# board-led.net
KiCad netlist of a schematic drawn in EAGLE
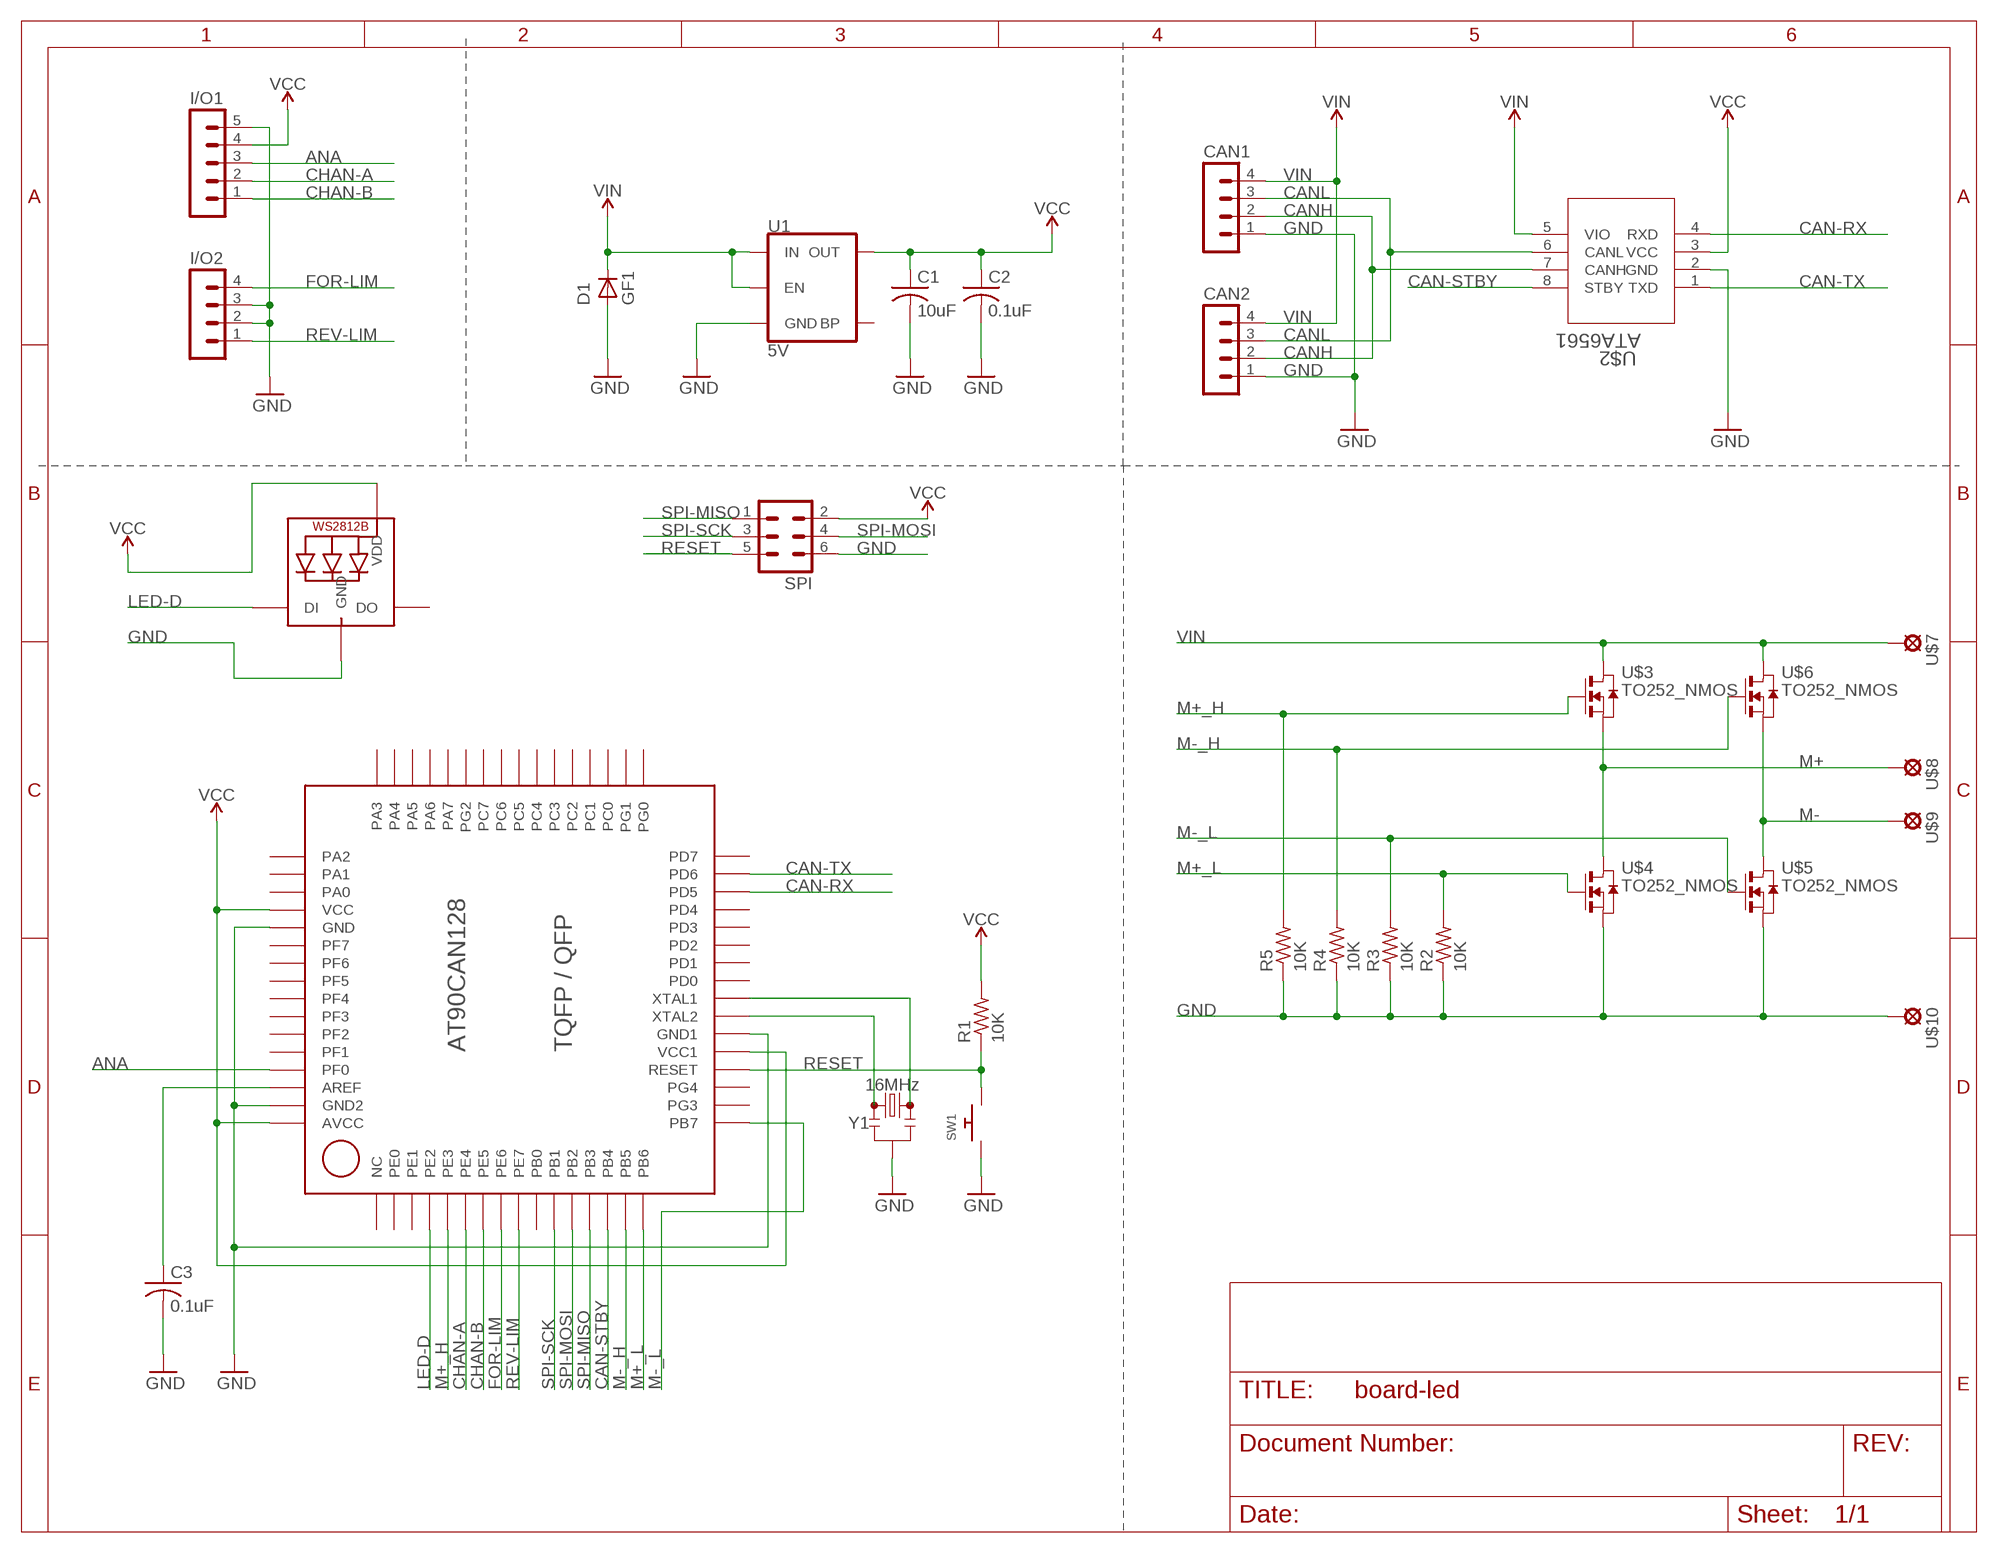
[diagram p0: schematic, sheet 1]

(export (version "E")
  (design (tool "Eeschema 10.0.6"))
  (components
    (comp (ref "C1")
      (value "10uF")
      (footprint "eagle-import:C0603")
      (libsource (lib "eagle-import") (part "C-USC0603"))
    )
    (comp (ref "C2")
      (value "0.1uF")
      (footprint "eagle-import:C0603")
      (libsource (lib "eagle-import") (part "C-USC0603"))
    )
    (comp (ref "C3")
      (value "0.1uF")
      (footprint "eagle-import:C0603")
      (libsource (lib "eagle-import") (part "C-USC0603"))
    )
    (comp (ref "CAN1")
      (value "MA04-1")
      (footprint "eagle-import:MA04-1")
      (libsource (lib "eagle-import") (part "MA04-1"))
    )
    (comp (ref "CAN2")
      (value "MA04-1")
      (footprint "eagle-import:MA04-1")
      (libsource (lib "eagle-import") (part "MA04-1"))
    )
    (comp (ref "D1")
      (value "GF1")
      (footprint "eagle-import:SMA-DO214AC")
      (libsource (lib "eagle-import") (part "GF1"))
    )
    (comp (ref "I/O1")
      (value "MA05-1")
      (footprint "eagle-import:MA05-1")
      (libsource (lib "eagle-import") (part "MA05-1"))
    )
    (comp (ref "I/O2")
      (value "MA04-1")
      (footprint "eagle-import:MA04-1")
      (libsource (lib "eagle-import") (part "MA04-1"))
    )
    (comp (ref "LED1")
      (value "WS2812B3535")
      (footprint "eagle-import:LED3535")
      (libsource (lib "eagle-import") (part "WS2812B3535"))
    )
    (comp (ref "R1")
      (value "10K")
      (footprint "eagle-import:R0603")
      (libsource (lib "eagle-import") (part "R-US_R0603"))
    )
    (comp (ref "R2")
      (value "10K")
      (footprint "eagle-import:R0603")
      (libsource (lib "eagle-import") (part "R-US_R0603"))
    )
    (comp (ref "R3")
      (value "10K")
      (footprint "eagle-import:R0603")
      (libsource (lib "eagle-import") (part "R-US_R0603"))
    )
    (comp (ref "R4")
      (value "10K")
      (footprint "eagle-import:R0603")
      (libsource (lib "eagle-import") (part "R-US_R0603"))
    )
    (comp (ref "R5")
      (value "10K")
      (footprint "eagle-import:R0603")
      (libsource (lib "eagle-import") (part "R-US_R0603"))
    )
    (comp (ref "SPI")
      (value "MA03-2")
      (footprint "eagle-import:MA03-2")
      (libsource (lib "eagle-import") (part "MA03-2"))
    )
    (comp (ref "SW1")
      (value "SWITCH_PUSHBUTTONEVQ-PE")
      (footprint "eagle-import:TACT_PANA-EVQ")
      (libsource (lib "eagle-import") (part "SWITCH_PUSHBUTTONEVQ-PE"))
    )
    (comp (ref "U$1")
      (value "AT90CAN128")
      (footprint "eagle-import:QFP64_TQFP64")
      (libsource (lib "eagle-import") (part "AT90CAN128"))
    )
    (comp (ref "U$2")
      (value "ATA6561")
      (footprint "eagle-import:SO8")
      (libsource (lib "eagle-import") (part "ATA6561"))
    )
    (comp (ref "U$3")
      (value "TO252_NMOS")
      (footprint "eagle-import:TO252")
      (libsource (lib "eagle-import") (part "TO252_NMOS"))
    )
    (comp (ref "U$4")
      (value "TO252_NMOS")
      (footprint "eagle-import:TO252")
      (libsource (lib "eagle-import") (part "TO252_NMOS"))
    )
    (comp (ref "U$5")
      (value "TO252_NMOS")
      (footprint "eagle-import:TO252")
      (libsource (lib "eagle-import") (part "TO252_NMOS"))
    )
    (comp (ref "U$6")
      (value "TO252_NMOS")
      (footprint "eagle-import:TO252")
      (libsource (lib "eagle-import") (part "TO252_NMOS"))
    )
    (comp (ref "U$7")
      (value "SOLPAD")
      (footprint "eagle-import:SOLPAD")
      (libsource (lib "eagle-import") (part "SOLPAD"))
    )
    (comp (ref "U$8")
      (value "SOLPAD")
      (footprint "eagle-import:SOLPAD")
      (libsource (lib "eagle-import") (part "SOLPAD"))
    )
    (comp (ref "U$9")
      (value "SOLPAD")
      (footprint "eagle-import:SOLPAD")
      (libsource (lib "eagle-import") (part "SOLPAD"))
    )
    (comp (ref "U$10")
      (value "SOLPAD")
      (footprint "eagle-import:SOLPAD")
      (libsource (lib "eagle-import") (part "SOLPAD"))
    )
    (comp (ref "U1")
      (value "5V")
      (footprint "eagle-import:SOT23-5")
      (libsource (lib "eagle-import") (part "V_REG_MIC52055V"))
    )
    (comp (ref "Y1")
      (value "16MHz")
      (footprint "eagle-import:RESONATOR-SMD-3.2X1.3")
      (libsource (lib "eagle-import") (part "RESONATOR-16MHZSMD_3.2X1.3"))
    )
  )
  (nets
    (net (code "1") (name "/ANA") (class "Default")
      (node (ref "I/O1") (pin "3") (pinfunction "3_3") (pintype "passive"))
      (node (ref "U$1") (pin "61") (pinfunction "PF0_61") (pintype "bidirectional"))
    )
    (net (code "2") (name "/CAN-RX") (class "Default")
      (node (ref "U$1") (pin "30") (pinfunction "PD5_30") (pintype "bidirectional"))
      (node (ref "U$2") (pin "4") (pinfunction "RXD_4") (pintype "input"))
    )
    (net (code "3") (name "/CAN-STBY") (class "Default")
      (node (ref "U$1") (pin "14") (pinfunction "PB4_14") (pintype "bidirectional"))
      (node (ref "U$2") (pin "8") (pinfunction "STBY_8") (pintype "passive"))
    )
    (net (code "4") (name "/CAN-TX") (class "Default")
      (node (ref "U$1") (pin "31") (pinfunction "PD6_31") (pintype "bidirectional"))
      (node (ref "U$2") (pin "1") (pinfunction "TXD_1") (pintype "power_in"))
    )
    (net (code "5") (name "/CANH") (class "Default")
      (node (ref "CAN1") (pin "2") (pinfunction "2_2") (pintype "passive"))
      (node (ref "CAN2") (pin "2") (pinfunction "2_2") (pintype "passive"))
      (node (ref "U$2") (pin "7") (pinfunction "CANH_7") (pintype "output"))
    )
    (net (code "6") (name "/CANL") (class "Default")
      (node (ref "CAN1") (pin "3") (pinfunction "3_3") (pintype "passive"))
      (node (ref "CAN2") (pin "3") (pinfunction "3_3") (pintype "passive"))
      (node (ref "U$2") (pin "6") (pinfunction "CANL_6") (pintype "output"))
    )
    (net (code "7") (name "/CHAN-A") (class "Default")
      (node (ref "I/O1") (pin "2") (pinfunction "2_2") (pintype "passive"))
      (node (ref "U$1") (pin "6") (pinfunction "PE4_6") (pintype "bidirectional"))
    )
    (net (code "8") (name "/CHAN-B") (class "Default")
      (node (ref "I/O1") (pin "1") (pinfunction "1_1") (pintype "passive"))
      (node (ref "U$1") (pin "7") (pinfunction "PE5_7") (pintype "bidirectional"))
    )
    (net (code "9") (name "/FOR-LIM") (class "Default")
      (node (ref "I/O2") (pin "4") (pinfunction "4_4") (pintype "passive"))
      (node (ref "U$1") (pin "8") (pinfunction "PE6_8") (pintype "bidirectional"))
    )
    (net (code "10") (name "/LED-D") (class "Default")
      (node (ref "LED1") (pin "1") (pinfunction "DI_1") (pintype "input"))
      (node (ref "U$1") (pin "4") (pinfunction "PE2_4") (pintype "bidirectional"))
    )
    (net (code "11") (name "/M+") (class "Default")
      (node (ref "U$3") (pin "2") (pinfunction "S_2") (pintype "passive"))
      (node (ref "U$4") (pin "3") (pinfunction "D_3") (pintype "passive"))
      (node (ref "U$8") (pin "P$1") (pinfunction "MP_P$1") (pintype "passive"))
    )
    (net (code "12") (name "/M+_H") (class "Default")
      (node (ref "R5") (pin "2") (pinfunction "2_2") (pintype "passive"))
      (node (ref "U$1") (pin "5") (pinfunction "PE3_5") (pintype "bidirectional"))
      (node (ref "U$3") (pin "1") (pinfunction "G_1") (pintype "passive"))
    )
    (net (code "13") (name "/M+_L") (class "Default")
      (node (ref "R2") (pin "2") (pinfunction "2_2") (pintype "passive"))
      (node (ref "U$1") (pin "16") (pinfunction "PB6_16") (pintype "bidirectional"))
      (node (ref "U$4") (pin "1") (pinfunction "G_1") (pintype "passive"))
    )
    (net (code "14") (name "/M-") (class "Default")
      (node (ref "U$5") (pin "3") (pinfunction "D_3") (pintype "passive"))
      (node (ref "U$6") (pin "2") (pinfunction "S_2") (pintype "passive"))
      (node (ref "U$9") (pin "P$1") (pinfunction "MP_P$1") (pintype "passive"))
    )
    (net (code "15") (name "/M-_H") (class "Default")
      (node (ref "R4") (pin "2") (pinfunction "2_2") (pintype "passive"))
      (node (ref "U$1") (pin "15") (pinfunction "PB5_15") (pintype "bidirectional"))
      (node (ref "U$6") (pin "1") (pinfunction "G_1") (pintype "passive"))
    )
    (net (code "16") (name "/M-_L") (class "Default")
      (node (ref "R3") (pin "2") (pinfunction "2_2") (pintype "passive"))
      (node (ref "U$1") (pin "17") (pinfunction "PB7_17") (pintype "bidirectional"))
      (node (ref "U$5") (pin "1") (pinfunction "G_1") (pintype "passive"))
    )
    (net (code "17") (name "/RESET") (class "Default")
      (node (ref "R1") (pin "1") (pinfunction "1_1") (pintype "passive"))
      (node (ref "SPI") (pin "5") (pinfunction "5_5") (pintype "passive"))
      (node (ref "SW1") (pin "P$2") (pinfunction "P$2_P$2") (pintype "passive"))
      (node (ref "U$1") (pin "20") (pinfunction "RESET_20") (pintype "bidirectional"))
    )
    (net (code "18") (name "/REV-LIM") (class "Default")
      (node (ref "I/O2") (pin "1") (pinfunction "1_1") (pintype "passive"))
      (node (ref "U$1") (pin "9") (pinfunction "PE7_9") (pintype "bidirectional"))
    )
    (net (code "19") (name "/SPI-MISO") (class "Default")
      (node (ref "SPI") (pin "1") (pinfunction "1_1") (pintype "passive"))
      (node (ref "U$1") (pin "13") (pinfunction "PB3_13") (pintype "bidirectional"))
    )
    (net (code "20") (name "/SPI-MOSI") (class "Default")
      (node (ref "SPI") (pin "4") (pinfunction "4_4") (pintype "passive"))
      (node (ref "U$1") (pin "12") (pinfunction "PB2_12") (pintype "bidirectional"))
    )
    (net (code "21") (name "/SPI-SCK") (class "Default")
      (node (ref "SPI") (pin "3") (pinfunction "3_3") (pintype "passive"))
      (node (ref "U$1") (pin "11") (pinfunction "PB1_11") (pintype "bidirectional"))
    )
    (net (code "22") (name "GND") (class "Default")
      (node (ref "C1") (pin "2") (pinfunction "2_2") (pintype "passive"))
      (node (ref "C2") (pin "2") (pinfunction "2_2") (pintype "passive"))
      (node (ref "C3") (pin "2") (pinfunction "2_2") (pintype "passive"))
      (node (ref "CAN1") (pin "1") (pinfunction "1_1") (pintype "passive"))
      (node (ref "CAN2") (pin "1") (pinfunction "1_1") (pintype "passive"))
      (node (ref "D1") (pin "A") (pinfunction "A_A") (pintype "passive"))
      (node (ref "I/O1") (pin "5") (pinfunction "5_5") (pintype "passive"))
      (node (ref "I/O2") (pin "2") (pinfunction "2_2") (pintype "passive"))
      (node (ref "I/O2") (pin "3") (pinfunction "3_3") (pintype "passive"))
      (node (ref "LED1") (pin "4") (pinfunction "GND_4") (pintype "power_in"))
      (node (ref "R2") (pin "1") (pinfunction "1_1") (pintype "passive"))
      (node (ref "R3") (pin "1") (pinfunction "1_1") (pintype "passive"))
      (node (ref "R4") (pin "1") (pinfunction "1_1") (pintype "passive"))
      (node (ref "R5") (pin "1") (pinfunction "1_1") (pintype "passive"))
      (node (ref "SPI") (pin "6") (pinfunction "6_6") (pintype "passive"))
      (node (ref "SW1") (pin "P$1") (pinfunction "P$1_P$1") (pintype "passive"))
      (node (ref "U$1") (pin "22") (pinfunction "GND1_22") (pintype "bidirectional"))
      (node (ref "U$1") (pin "53") (pinfunction "GND_53") (pintype "bidirectional"))
      (node (ref "U$1") (pin "63") (pinfunction "GND2_63") (pintype "bidirectional"))
      (node (ref "U$10") (pin "P$1") (pinfunction "MP_P$1") (pintype "passive"))
      (node (ref "U$2") (pin "2") (pinfunction "GND_2") (pintype "input"))
      (node (ref "U$4") (pin "2") (pinfunction "S_2") (pintype "passive"))
      (node (ref "U$5") (pin "2") (pinfunction "S_2") (pintype "passive"))
      (node (ref "U1") (pin "2") (pinfunction "GND_2") (pintype "input"))
      (node (ref "Y1") (pin "2") (pinfunction "2_2") (pintype "passive"))
    )
    (net (code "23") (name "Net-(U$1-AREF)") (class "Default")
      (node (ref "C3") (pin "1") (pinfunction "1_1") (pintype "passive"))
      (node (ref "U$1") (pin "62") (pinfunction "AREF_62") (pintype "bidirectional"))
    )
    (net (code "24") (name "Net-(U$1-XTAL1)") (class "Default")
      (node (ref "U$1") (pin "24") (pinfunction "XTAL1_24") (pintype "bidirectional"))
      (node (ref "Y1") (pin "3") (pinfunction "3_3") (pintype "passive"))
    )
    (net (code "25") (name "Net-(U$1-XTAL2)") (class "Default")
      (node (ref "U$1") (pin "23") (pinfunction "XTAL2_23") (pintype "bidirectional"))
      (node (ref "Y1") (pin "1") (pinfunction "1_1") (pintype "passive"))
    )
    (net (code "26") (name "VCC") (class "Default")
      (node (ref "C1") (pin "1") (pinfunction "1_1") (pintype "passive"))
      (node (ref "C2") (pin "1") (pinfunction "1_1") (pintype "passive"))
      (node (ref "I/O1") (pin "4") (pinfunction "4_4") (pintype "passive"))
      (node (ref "LED1") (pin "2") (pinfunction "VDD_2") (pintype "power_in"))
      (node (ref "R1") (pin "2") (pinfunction "2_2") (pintype "passive"))
      (node (ref "SPI") (pin "2") (pinfunction "2_2") (pintype "passive"))
      (node (ref "U$1") (pin "21") (pinfunction "VCC1_21") (pintype "bidirectional"))
      (node (ref "U$1") (pin "52") (pinfunction "VCC_52") (pintype "bidirectional"))
      (node (ref "U$1") (pin "64") (pinfunction "AVCC_64") (pintype "bidirectional"))
      (node (ref "U$2") (pin "3") (pinfunction "VCC_3") (pintype "input"))
      (node (ref "U1") (pin "5") (pinfunction "OUT_5") (pintype "passive"))
    )
    (net (code "27") (name "VIN") (class "Default")
      (node (ref "CAN1") (pin "4") (pinfunction "4_4") (pintype "passive"))
      (node (ref "CAN2") (pin "4") (pinfunction "4_4") (pintype "passive"))
      (node (ref "D1") (pin "K") (pinfunction "C_K") (pintype "passive"))
      (node (ref "U$2") (pin "5") (pinfunction "VIO_5") (pintype "passive"))
      (node (ref "U$3") (pin "3") (pinfunction "D_3") (pintype "passive"))
      (node (ref "U$6") (pin "3") (pinfunction "D_3") (pintype "passive"))
      (node (ref "U$7") (pin "P$1") (pinfunction "MP_P$1") (pintype "passive"))
      (node (ref "U1") (pin "1") (pinfunction "IN_1") (pintype "input"))
      (node (ref "U1") (pin "3") (pinfunction "EN_3") (pintype "input"))
    )
    (net (code "28") (name "unconnected-(LED1-DO-Pad3)") (class "Default")
      (node (ref "LED1") (pin "3") (pinfunction "DO_3") (pintype "output"))
    )
    (net (code "29") (name "unconnected-(U$1-NC-Pad1)") (class "Default")
      (node (ref "U$1") (pin "1") (pinfunction "NC_1") (pintype "bidirectional"))
    )
    (net (code "30") (name "unconnected-(U$1-PA0-Pad51)") (class "Default")
      (node (ref "U$1") (pin "51") (pinfunction "PA0_51") (pintype "bidirectional"))
    )
    (net (code "31") (name "unconnected-(U$1-PA1-Pad50)") (class "Default")
      (node (ref "U$1") (pin "50") (pinfunction "PA1_50") (pintype "bidirectional"))
    )
    (net (code "32") (name "unconnected-(U$1-PA2-Pad49)") (class "Default")
      (node (ref "U$1") (pin "49") (pinfunction "PA2_49") (pintype "bidirectional"))
    )
    (net (code "33") (name "unconnected-(U$1-PA3-Pad48)") (class "Default")
      (node (ref "U$1") (pin "48") (pinfunction "PA3_48") (pintype "bidirectional"))
    )
    (net (code "34") (name "unconnected-(U$1-PA4-Pad47)") (class "Default")
      (node (ref "U$1") (pin "47") (pinfunction "PA4_47") (pintype "bidirectional"))
    )
    (net (code "35") (name "unconnected-(U$1-PA5-Pad46)") (class "Default")
      (node (ref "U$1") (pin "46") (pinfunction "PA5_46") (pintype "bidirectional"))
    )
    (net (code "36") (name "unconnected-(U$1-PA6-Pad45)") (class "Default")
      (node (ref "U$1") (pin "45") (pinfunction "PA6_45") (pintype "bidirectional"))
    )
    (net (code "37") (name "unconnected-(U$1-PA7-Pad44)") (class "Default")
      (node (ref "U$1") (pin "44") (pinfunction "PA7_44") (pintype "bidirectional"))
    )
    (net (code "38") (name "unconnected-(U$1-PB0-Pad10)") (class "Default")
      (node (ref "U$1") (pin "10") (pinfunction "PB0_10") (pintype "bidirectional"))
    )
    (net (code "39") (name "unconnected-(U$1-PC0-Pad35)") (class "Default")
      (node (ref "U$1") (pin "35") (pinfunction "PC0_35") (pintype "bidirectional"))
    )
    (net (code "40") (name "unconnected-(U$1-PC1-Pad36)") (class "Default")
      (node (ref "U$1") (pin "36") (pinfunction "PC1_36") (pintype "bidirectional"))
    )
    (net (code "41") (name "unconnected-(U$1-PC2-Pad37)") (class "Default")
      (node (ref "U$1") (pin "37") (pinfunction "PC2_37") (pintype "bidirectional"))
    )
    (net (code "42") (name "unconnected-(U$1-PC3-Pad38)") (class "Default")
      (node (ref "U$1") (pin "38") (pinfunction "PC3_38") (pintype "bidirectional"))
    )
    (net (code "43") (name "unconnected-(U$1-PC4-Pad39)") (class "Default")
      (node (ref "U$1") (pin "39") (pinfunction "PC4_39") (pintype "bidirectional"))
    )
    (net (code "44") (name "unconnected-(U$1-PC5-Pad40)") (class "Default")
      (node (ref "U$1") (pin "40") (pinfunction "PC5_40") (pintype "bidirectional"))
    )
    (net (code "45") (name "unconnected-(U$1-PC6-Pad41)") (class "Default")
      (node (ref "U$1") (pin "41") (pinfunction "PC6_41") (pintype "bidirectional"))
    )
    (net (code "46") (name "unconnected-(U$1-PC7-Pad42)") (class "Default")
      (node (ref "U$1") (pin "42") (pinfunction "PC7_42") (pintype "bidirectional"))
    )
    (net (code "47") (name "unconnected-(U$1-PD0-Pad25)") (class "Default")
      (node (ref "U$1") (pin "25") (pinfunction "PD0_25") (pintype "bidirectional"))
    )
    (net (code "48") (name "unconnected-(U$1-PD1-Pad26)") (class "Default")
      (node (ref "U$1") (pin "26") (pinfunction "PD1_26") (pintype "bidirectional"))
    )
    (net (code "49") (name "unconnected-(U$1-PD2-Pad27)") (class "Default")
      (node (ref "U$1") (pin "27") (pinfunction "PD2_27") (pintype "bidirectional"))
    )
    (net (code "50") (name "unconnected-(U$1-PD3-Pad28)") (class "Default")
      (node (ref "U$1") (pin "28") (pinfunction "PD3_28") (pintype "bidirectional"))
    )
    (net (code "51") (name "unconnected-(U$1-PD4-Pad29)") (class "Default")
      (node (ref "U$1") (pin "29") (pinfunction "PD4_29") (pintype "bidirectional"))
    )
    (net (code "52") (name "unconnected-(U$1-PD7-Pad32)") (class "Default")
      (node (ref "U$1") (pin "32") (pinfunction "PD7_32") (pintype "bidirectional"))
    )
    (net (code "53") (name "unconnected-(U$1-PE0-Pad2)") (class "Default")
      (node (ref "U$1") (pin "2") (pinfunction "PE0_2") (pintype "bidirectional"))
    )
    (net (code "54") (name "unconnected-(U$1-PE1-Pad3)") (class "Default")
      (node (ref "U$1") (pin "3") (pinfunction "PE1_3") (pintype "bidirectional"))
    )
    (net (code "55") (name "unconnected-(U$1-PF1-Pad60)") (class "Default")
      (node (ref "U$1") (pin "60") (pinfunction "PF1_60") (pintype "bidirectional"))
    )
    (net (code "56") (name "unconnected-(U$1-PF2-Pad59)") (class "Default")
      (node (ref "U$1") (pin "59") (pinfunction "PF2_59") (pintype "bidirectional"))
    )
    (net (code "57") (name "unconnected-(U$1-PF3-Pad58)") (class "Default")
      (node (ref "U$1") (pin "58") (pinfunction "PF3_58") (pintype "bidirectional"))
    )
    (net (code "58") (name "unconnected-(U$1-PF4-Pad57)") (class "Default")
      (node (ref "U$1") (pin "57") (pinfunction "PF4_57") (pintype "bidirectional"))
    )
    (net (code "59") (name "unconnected-(U$1-PF5-Pad56)") (class "Default")
      (node (ref "U$1") (pin "56") (pinfunction "PF5_56") (pintype "bidirectional"))
    )
    (net (code "60") (name "unconnected-(U$1-PF6-Pad55)") (class "Default")
      (node (ref "U$1") (pin "55") (pinfunction "PF6_55") (pintype "bidirectional"))
    )
    (net (code "61") (name "unconnected-(U$1-PF7-Pad54)") (class "Default")
      (node (ref "U$1") (pin "54") (pinfunction "PF7_54") (pintype "bidirectional"))
    )
    (net (code "62") (name "unconnected-(U$1-PG0-Pad33)") (class "Default")
      (node (ref "U$1") (pin "33") (pinfunction "PG0_33") (pintype "bidirectional"))
    )
    (net (code "63") (name "unconnected-(U$1-PG1-Pad34)") (class "Default")
      (node (ref "U$1") (pin "34") (pinfunction "PG1_34") (pintype "bidirectional"))
    )
    (net (code "64") (name "unconnected-(U$1-PG2-Pad43)") (class "Default")
      (node (ref "U$1") (pin "43") (pinfunction "PG2_43") (pintype "bidirectional"))
    )
    (net (code "65") (name "unconnected-(U$1-PG3-Pad18)") (class "Default")
      (node (ref "U$1") (pin "18") (pinfunction "PG3_18") (pintype "bidirectional"))
    )
    (net (code "66") (name "unconnected-(U$1-PG4-Pad19)") (class "Default")
      (node (ref "U$1") (pin "19") (pinfunction "PG4_19") (pintype "bidirectional"))
    )
    (net (code "67") (name "unconnected-(U1-BP-Pad4)") (class "Default")
      (node (ref "U1") (pin "4") (pinfunction "BP_4") (pintype "input"))
    )
  )
)
